# STM32.net
KiCad netlist of a schematic drawn in Altium Designer
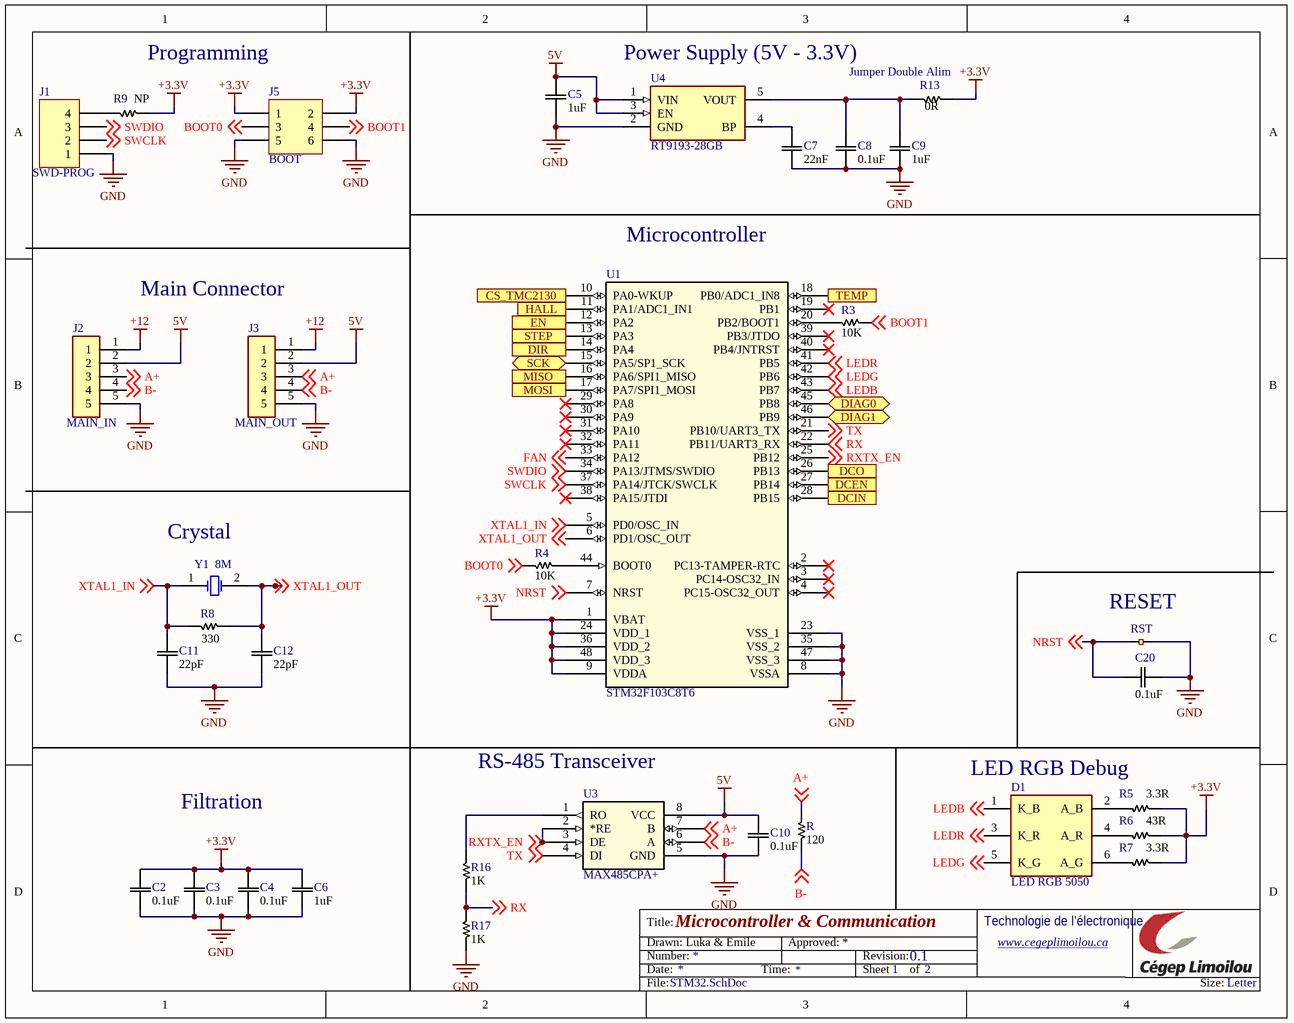
[diagram p0: STM32.SchDoc]

(export (version "E")
  (design (tool "Eeschema 10.0.6"))
  (components
    (comp (ref "C2")
      (value "0.1uF")
      (footprint "0603")
      (description "Capacitor SMD 0603")
      (fields
        (field (name "MANUFACTURER_PART_NUMBER") "12065A820JAT2A")
        (field (name "Comment") "Capacitor 0603")
        (field (name "COPYRIGHT") "Copyright (C) 2018 Accelerated Designs. All rights reserved")
      )
      (libsource (lib "Schematic_Emile") (part "Capacitor 1206"))
    )
    (comp (ref "C3")
      (value "0.1uF")
      (footprint "0603")
      (description "Capacitor SMD 0603")
      (fields
        (field (name "MANUFACTURER_PART_NUMBER") "12065A820JAT2A")
        (field (name "Comment") "Capacitor 0603")
        (field (name "COPYRIGHT") "Copyright (C) 2018 Accelerated Designs. All rights reserved")
      )
      (libsource (lib "Schematic_Emile") (part "Capacitor 1206"))
    )
    (comp (ref "C4")
      (value "0.1uF")
      (footprint "0603")
      (description "Capacitor SMD 0603")
      (fields
        (field (name "MANUFACTURER_PART_NUMBER") "12065A820JAT2A")
        (field (name "Comment") "Capacitor 0603")
        (field (name "COPYRIGHT") "Copyright (C) 2018 Accelerated Designs. All rights reserved")
      )
      (libsource (lib "Schematic_Emile") (part "Capacitor 1206"))
    )
    (comp (ref "C5")
      (value "1uF")
      (footprint "0603")
      (description "Capacitor SMD 0603")
      (fields
        (field (name "MANUFACTURER_PART_NUMBER") "12065A820JAT2A")
        (field (name "Comment") "Capacitor 0603")
        (field (name "COPYRIGHT") "Copyright (C) 2018 Accelerated Designs. All rights reserved")
      )
      (libsource (lib "Schematic_Emile") (part "Capacitor 1206"))
    )
    (comp (ref "C6")
      (value "1uF")
      (footprint "0603")
      (description "Capacitor SMD 0603")
      (fields
        (field (name "MANUFACTURER_PART_NUMBER") "12065A820JAT2A")
        (field (name "Comment") "Capacitor 0603")
        (field (name "COPYRIGHT") "Copyright (C) 2018 Accelerated Designs. All rights reserved")
      )
      (libsource (lib "Schematic_Emile") (part "Capacitor 1206"))
    )
    (comp (ref "C7")
      (value "22nF")
      (footprint "0603")
      (description "Capacitor SMD 0603")
      (fields
        (field (name "MANUFACTURER_PART_NUMBER") "12065A820JAT2A")
        (field (name "Comment") "Capacitor 0603")
        (field (name "COPYRIGHT") "Copyright (C) 2018 Accelerated Designs. All rights reserved")
      )
      (libsource (lib "Schematic_Emile") (part "Capacitor 1206"))
    )
    (comp (ref "C8")
      (value "0.1uF")
      (footprint "0603")
      (description "Capacitor SMD 0603")
      (fields
        (field (name "MANUFACTURER_PART_NUMBER") "12065A820JAT2A")
        (field (name "Comment") "Capacitor 0603")
        (field (name "COPYRIGHT") "Copyright (C) 2018 Accelerated Designs. All rights reserved")
      )
      (libsource (lib "Schematic_Emile") (part "Capacitor 1206"))
    )
    (comp (ref "C9")
      (value "1uF")
      (footprint "0603")
      (description "Capacitor SMD 0603")
      (fields
        (field (name "MANUFACTURER_PART_NUMBER") "12065A820JAT2A")
        (field (name "Comment") "Capacitor 0603")
        (field (name "COPYRIGHT") "Copyright (C) 2018 Accelerated Designs. All rights reserved")
      )
      (libsource (lib "Schematic_Emile") (part "Capacitor 1206"))
    )
    (comp (ref "C10")
      (value "0.1uF")
      (footprint "0603")
      (description "Capacitor SMD 0603")
      (fields
        (field (name "MANUFACTURER_PART_NUMBER") "12065A820JAT2A")
        (field (name "Comment") "Capacitor 0603")
        (field (name "COPYRIGHT") "Copyright (C) 2018 Accelerated Designs. All rights reserved")
      )
      (libsource (lib "Schematic_Emile") (part "Capacitor 1206"))
    )
    (comp (ref "C11")
      (value "22pF")
      (footprint "0603")
      (description "Capacitor SMD 0603")
      (fields
        (field (name "MANUFACTURER_PART_NUMBER") "12065A820JAT2A")
        (field (name "Comment") "Capacitor 0603")
        (field (name "COPYRIGHT") "Copyright (C) 2018 Accelerated Designs. All rights reserved")
      )
      (libsource (lib "Schematic_Emile") (part "Capacitor 1206"))
    )
    (comp (ref "C12")
      (value "22pF")
      (footprint "0603")
      (description "Capacitor SMD 0603")
      (fields
        (field (name "MANUFACTURER_PART_NUMBER") "12065A820JAT2A")
        (field (name "Comment") "Capacitor 0603")
        (field (name "COPYRIGHT") "Copyright (C) 2018 Accelerated Designs. All rights reserved")
      )
      (libsource (lib "Schematic_Emile") (part "Capacitor 1206"))
    )
    (comp (ref "C20")
      (value "0.1uF")
      (footprint "0603")
      (description "Capacitor SMD 0603")
      (fields
        (field (name "MANUFACTURER_PART_NUMBER") "12065A820JAT2A")
        (field (name "Comment") "Capacitor 0603")
        (field (name "COPYRIGHT") "Copyright (C) 2018 Accelerated Designs. All rights reserved")
      )
      (libsource (lib "Schematic_Emile") (part "Capacitor 1206"))
    )
    (comp (ref "D1")
      (value "LED RGB 5050")
      (footprint "LED 5050")
      (description "LED")
      (fields
        (field (name "MANUFACTURER_PART_NUMBER") "150505M173300")
        (field (name "MOUSER PART NUMBER") "710-150505M173300")
      )
      (libsource (lib "Schematic_Emile") (part "150505M173300"))
    )
    (comp (ref "J1")
      (value "SWD-PROG")
      (footprint "HDR1X4")
      (description "Header, 4-Pin")
      (fields (field (name "PUBLISHER") "Altium Limited"))
      (libsource (lib "Miscellaneous Connectors") (part "Header 4"))
    )
    (comp (ref "J2")
      (value "MAIN_IN")
      (footprint "JST 5POS 2.5mm 90°")
      (description "Connector")
      (fields (field (name "MANUFACTURER_PART_NUMBER") "S5B-XH-A-1(LF)(SN)"))
      (libsource (lib "Schematic_Emile") (part "JST 5POS"))
    )
    (comp (ref "J3")
      (value "MAIN_OUT")
      (footprint "JST 5POS 2.5mm 90°")
      (description "Connector")
      (fields (field (name "MANUFACTURER_PART_NUMBER") "S5B-XH-A-1(LF)(SN)"))
      (libsource (lib "Schematic_Emile") (part "JST 5POS"))
    )
    (comp (ref "J5")
      (value "BOOT")
      (footprint "Header 3x2 1.27mm SMD")
      (description "Header, 3-Pin, Dual row")
      (fields (field (name "PUBLISHER") "Altium Limited"))
      (libsource (lib "Miscellaneous Connectors") (part "Header 3X2"))
    )
    (comp (ref "R")
      (value "120")
      (footprint "0603")
      (description "Resistor 0603 SMD")
      (fields
        (field (name "MANUFACTURER_PART_NUMBER") "ERJ8CWFR024V")
        (field (name "Comment") "Resistor 0603")
        (field (name "COPYRIGHT") "Copyright (C) 2018 Accelerated Designs. All rights reserved")
      )
      (libsource (lib "Schematic_Emile") (part "Resistor 1206"))
    )
    (comp (ref "R3")
      (value "10K")
      (footprint "0603")
      (description "Resistor 0603 SMD")
      (fields
        (field (name "MANUFACTURER_PART_NUMBER") "ERJ8CWFR024V")
        (field (name "Comment") "Resistor 0603")
        (field (name "COPYRIGHT") "Copyright (C) 2018 Accelerated Designs. All rights reserved")
      )
      (libsource (lib "Schematic_Emile") (part "Resistor 1206"))
    )
    (comp (ref "R4")
      (value "10K")
      (footprint "0603")
      (description "Resistor 0603 SMD")
      (fields
        (field (name "MANUFACTURER_PART_NUMBER") "ERJ8CWFR024V")
        (field (name "Comment") "Resistor 0603")
        (field (name "COPYRIGHT") "Copyright (C) 2018 Accelerated Designs. All rights reserved")
      )
      (libsource (lib "Schematic_Emile") (part "Resistor 1206"))
    )
    (comp (ref "R5")
      (value "3.3R")
      (footprint "0603")
      (description "Resistor 0603 SMD")
      (fields
        (field (name "MANUFACTURER_PART_NUMBER") "ERJ8CWFR024V")
        (field (name "Comment") "Resistor 0603")
        (field (name "COPYRIGHT") "Copyright (C) 2018 Accelerated Designs. All rights reserved")
      )
      (libsource (lib "Schematic_Emile") (part "Resistor 1206"))
    )
    (comp (ref "R6")
      (value "43R")
      (footprint "0603")
      (description "Resistor 0603 SMD")
      (fields
        (field (name "MANUFACTURER_PART_NUMBER") "ERJ8CWFR024V")
        (field (name "Comment") "Resistor 0603")
        (field (name "COPYRIGHT") "Copyright (C) 2018 Accelerated Designs. All rights reserved")
      )
      (libsource (lib "Schematic_Emile") (part "Resistor 1206"))
    )
    (comp (ref "R7")
      (value "3.3R")
      (footprint "0603")
      (description "Resistor 0603 SMD")
      (fields
        (field (name "MANUFACTURER_PART_NUMBER") "ERJ8CWFR024V")
        (field (name "Comment") "Resistor 0603")
        (field (name "COPYRIGHT") "Copyright (C) 2018 Accelerated Designs. All rights reserved")
      )
      (libsource (lib "Schematic_Emile") (part "Resistor 1206"))
    )
    (comp (ref "R8")
      (value "330")
      (footprint "0603")
      (description "Resistor 0603 SMD")
      (fields
        (field (name "MANUFACTURER_PART_NUMBER") "ERJ8CWFR024V")
        (field (name "Comment") "Resistor 0603")
        (field (name "COPYRIGHT") "Copyright (C) 2018 Accelerated Designs. All rights reserved")
      )
      (libsource (lib "Schematic_Emile") (part "Resistor 1206"))
    )
    (comp (ref "R9")
      (value "NP")
      (footprint "0603")
      (description "Resistor 0603 SMD")
      (fields
        (field (name "MANUFACTURER_PART_NUMBER") "ERJ8CWFR024V")
        (field (name "Comment") "Jumper 0603")
        (field (name "COPYRIGHT") "Copyright (C) 2018 Accelerated Designs. All rights reserved")
      )
      (libsource (lib "Schematic_Emile") (part "Resistor 1206"))
    )
    (comp (ref "R13")
      (value "0R")
      (footprint "0603")
      (description "Resistor 1206 SMD")
      (fields
        (field (name "MANUFACTURER_PART_NUMBER") "ERJ8CWFR024V")
        (field (name "Comment") "Jumper 0603")
        (field (name "COPYRIGHT") "Copyright (C) 2018 Accelerated Designs. All rights reserved")
      )
      (libsource (lib "Schematic_Emile") (part "Resistor 1206"))
    )
    (comp (ref "R16")
      (value "1K")
      (footprint "0603")
      (description "Resistor 0603 SMD")
      (fields
        (field (name "MANUFACTURER_PART_NUMBER") "ERJ8CWFR024V")
        (field (name "Comment") "Resistor 0603")
        (field (name "COPYRIGHT") "Copyright (C) 2018 Accelerated Designs. All rights reserved")
      )
      (libsource (lib "Schematic_Emile") (part "Resistor 1206"))
    )
    (comp (ref "R17")
      (value "1K")
      (footprint "0603")
      (description "Resistor 0603 SMD")
      (fields
        (field (name "MANUFACTURER_PART_NUMBER") "ERJ8CWFR024V")
        (field (name "Comment") "Resistor 0603")
        (field (name "COPYRIGHT") "Copyright (C) 2018 Accelerated Designs. All rights reserved")
      )
      (libsource (lib "Schematic_Emile") (part "Resistor 1206"))
    )
    (comp (ref "RST")
      (value "PAD RST")
      (footprint "PAD")
      (description "SMD Pad for contact")
      (libsource (lib "Schematic_Emile") (part "PAD"))
    )
    (comp (ref "U1")
      (value "STM32F103C8T6")
      (footprint "LQFP-48")
      (description "Integrated Circuit STM32")
      (fields (field (name "COPYRIGHT") "Copyright (C) 2018 Accelerated Designs. All rights reserved"))
      (libsource (lib "Schematic_Emile") (part "STM32F103C8T6"))
    )
    (comp (ref "U3")
      (value "MAX485CPA+")
      (footprint "DIP 8 - 3D")
      (description "RS485 Communication")
      (fields (field (name "COPYRIGHT") "Copyright (C) 2018 Accelerated Designs. All rights reserved"))
      (libsource (lib "Schematic_Emile") (part "MAX485CPA+"))
    )
    (comp (ref "U4")
      (value "RT9193-28GB")
      (footprint "SamacSys:SOT94P279X130-5N")
      (description "Voltage Regulator 3.3V")
      (libsource (lib "Schematic_Emile") (part "RT9193-28GB"))
    )
    (comp (ref "Y1")
      (value "8M")
      (footprint "ATS080B-E")
      (description "Crystal Oscillator")
      (fields (field (name "PUBLISHER") "Altium Limited"))
      (libsource (lib "Miscellaneous Devices") (part "XTAL"))
    )
  )
  (nets
    (net (code "1") (name "+3.3V") (class "Default")
      (node (ref "C2") (pin "2") (pinfunction "2_2") (pintype "passive"))
      (node (ref "C3") (pin "2") (pinfunction "2_2") (pintype "passive"))
      (node (ref "C4") (pin "2") (pinfunction "2_2") (pintype "passive"))
      (node (ref "C6") (pin "2") (pinfunction "2_2") (pintype "passive"))
      (node (ref "J5") (pin "1") (pinfunction "1_1") (pintype "passive"))
      (node (ref "J5") (pin "2") (pinfunction "2_2") (pintype "passive"))
      (node (ref "R13") (pin "2") (pinfunction "2_2") (pintype "passive"))
      (node (ref "R5") (pin "2") (pinfunction "2_2") (pintype "passive"))
      (node (ref "R6") (pin "2") (pinfunction "2_2") (pintype "passive"))
      (node (ref "R7") (pin "2") (pinfunction "2_2") (pintype "passive"))
      (node (ref "R9") (pin "2") (pinfunction "2_2") (pintype "passive"))
      (node (ref "U1") (pin "1") (pinfunction "VBAT_1") (pintype "power_in"))
      (node (ref "U1") (pin "24") (pinfunction "VDD_1_24") (pintype "power_in"))
      (node (ref "U1") (pin "36") (pinfunction "VDD_2_36") (pintype "power_in"))
      (node (ref "U1") (pin "48") (pinfunction "VDD_3_48") (pintype "power_in"))
      (node (ref "U1") (pin "9") (pinfunction "VDDA_9") (pintype "power_in"))
    )
    (net (code "2") (name "+12") (class "Default")
      (node (ref "J2") (pin "1") (pinfunction "1_1") (pintype "passive"))
      (node (ref "J3") (pin "1") (pinfunction "1_1") (pintype "passive"))
    )
    (net (code "3") (name "/CS_TMC2130") (class "Default")
      (node (ref "U1") (pin "10") (pinfunction "PA0-WKUP_10") (pintype "bidirectional"))
    )
    (net (code "4") (name "/DCEN") (class "Default")
      (node (ref "U1") (pin "27") (pinfunction "PB14_27") (pintype "bidirectional"))
    )
    (net (code "5") (name "/DCIN") (class "Default")
      (node (ref "U1") (pin "28") (pinfunction "PB15_28") (pintype "bidirectional"))
    )
    (net (code "6") (name "/DCO") (class "Default")
      (node (ref "U1") (pin "26") (pinfunction "PB13_26") (pintype "bidirectional"))
    )
    (net (code "7") (name "/DIAG0") (class "Default")
      (node (ref "U1") (pin "45") (pinfunction "PB8_45") (pintype "bidirectional"))
    )
    (net (code "8") (name "/DIAG1") (class "Default")
      (node (ref "U1") (pin "46") (pinfunction "PB9_46") (pintype "bidirectional"))
    )
    (net (code "9") (name "/DIR") (class "Default")
      (node (ref "U1") (pin "14") (pinfunction "PA4_14") (pintype "bidirectional"))
    )
    (net (code "10") (name "/EN") (class "Default")
      (node (ref "U1") (pin "12") (pinfunction "PA2_12") (pintype "bidirectional"))
    )
    (net (code "11") (name "/HALL") (class "Default")
      (node (ref "U1") (pin "11") (pinfunction "PA1/ADC1_IN1_11") (pintype "bidirectional"))
    )
    (net (code "12") (name "/MISO") (class "Default")
      (node (ref "U1") (pin "16") (pinfunction "PA6/SPI1_MISO_16") (pintype "bidirectional"))
    )
    (net (code "13") (name "/MOSI") (class "Default")
      (node (ref "U1") (pin "17") (pinfunction "PA7/SPI1_MOSI_17") (pintype "bidirectional"))
    )
    (net (code "14") (name "/SCK") (class "Default")
      (node (ref "U1") (pin "15") (pinfunction "PA5/SP1_SCK_15") (pintype "bidirectional"))
    )
    (net (code "15") (name "/STEP") (class "Default")
      (node (ref "U1") (pin "13") (pinfunction "PA3_13") (pintype "bidirectional"))
    )
    (net (code "16") (name "/TEMP") (class "Default")
      (node (ref "U1") (pin "18") (pinfunction "PB0/ADC1_IN8_18") (pintype "bidirectional"))
    )
    (net (code "17") (name "5V") (class "Default")
      (node (ref "C10") (pin "2") (pinfunction "2_2") (pintype "passive"))
      (node (ref "C5") (pin "2") (pinfunction "2_2") (pintype "passive"))
      (node (ref "J2") (pin "2") (pinfunction "2_2") (pintype "passive"))
      (node (ref "J3") (pin "2") (pinfunction "2_2") (pintype "passive"))
      (node (ref "U3") (pin "8") (pinfunction "VCC_8") (pintype "power_in"))
      (node (ref "U4") (pin "1") (pinfunction "VIN_1") (pintype "input"))
      (node (ref "U4") (pin "3") (pinfunction "EN_3") (pintype "input"))
    )
    (net (code "18") (name "A+") (class "Default")
      (node (ref "J2") (pin "3") (pinfunction "3_3") (pintype "passive"))
      (node (ref "J3") (pin "3") (pinfunction "3_3") (pintype "passive"))
      (node (ref "R") (pin "2") (pinfunction "2_2") (pintype "passive"))
      (node (ref "U3") (pin "7") (pinfunction "B_7") (pintype "bidirectional"))
    )
    (net (code "19") (name "B-") (class "Default")
      (node (ref "J2") (pin "4") (pinfunction "4_4") (pintype "passive"))
      (node (ref "J3") (pin "4") (pinfunction "4_4") (pintype "passive"))
      (node (ref "R") (pin "1") (pinfunction "1_1") (pintype "passive"))
      (node (ref "U3") (pin "6") (pinfunction "A_6") (pintype "bidirectional"))
    )
    (net (code "20") (name "BOOT0") (class "Default")
      (node (ref "J5") (pin "3") (pinfunction "3_3") (pintype "passive"))
      (node (ref "R4") (pin "1") (pinfunction "1_1") (pintype "passive"))
    )
    (net (code "21") (name "BOOT1") (class "Default")
      (node (ref "J5") (pin "4") (pinfunction "4_4") (pintype "passive"))
      (node (ref "R3") (pin "2") (pinfunction "2_2") (pintype "passive"))
    )
    (net (code "22") (name "FAN") (class "Default")
      (node (ref "U1") (pin "33") (pinfunction "PA12_33") (pintype "bidirectional"))
    )
    (net (code "23") (name "GND") (class "Default")
      (node (ref "C10") (pin "1") (pinfunction "1_1") (pintype "passive"))
      (node (ref "C11") (pin "1") (pinfunction "1_1") (pintype "passive"))
      (node (ref "C12") (pin "1") (pinfunction "1_1") (pintype "passive"))
      (node (ref "C2") (pin "1") (pinfunction "1_1") (pintype "passive"))
      (node (ref "C20") (pin "1") (pinfunction "1_1") (pintype "passive"))
      (node (ref "C3") (pin "1") (pinfunction "1_1") (pintype "passive"))
      (node (ref "C4") (pin "1") (pinfunction "1_1") (pintype "passive"))
      (node (ref "C5") (pin "1") (pinfunction "1_1") (pintype "passive"))
      (node (ref "C6") (pin "1") (pinfunction "1_1") (pintype "passive"))
      (node (ref "C7") (pin "1") (pinfunction "1_1") (pintype "passive"))
      (node (ref "C8") (pin "1") (pinfunction "1_1") (pintype "passive"))
      (node (ref "C9") (pin "1") (pinfunction "1_1") (pintype "passive"))
      (node (ref "J1") (pin "1") (pinfunction "1_1") (pintype "passive"))
      (node (ref "J2") (pin "5") (pinfunction "5_5") (pintype "passive"))
      (node (ref "J3") (pin "5") (pinfunction "5_5") (pintype "passive"))
      (node (ref "J5") (pin "5") (pinfunction "5_5") (pintype "passive"))
      (node (ref "J5") (pin "6") (pinfunction "6_6") (pintype "passive"))
      (node (ref "R17") (pin "2") (pinfunction "2_2") (pintype "passive"))
      (node (ref "RST") (pin "1") (pinfunction "1_1") (pintype "passive"))
      (node (ref "U1") (pin "23") (pinfunction "VSS_1_23") (pintype "power_in"))
      (node (ref "U1") (pin "35") (pinfunction "VSS_2_35") (pintype "power_in"))
      (node (ref "U1") (pin "47") (pinfunction "VSS_3_47") (pintype "power_in"))
      (node (ref "U1") (pin "8") (pinfunction "VSSA_8") (pintype "power_in"))
      (node (ref "U3") (pin "5") (pinfunction "GND_5") (pintype "power_in"))
      (node (ref "U4") (pin "2") (pinfunction "GND_2") (pintype "power_in"))
    )
    (net (code "24") (name "LEDB") (class "Default")
      (node (ref "D1") (pin "1") (pinfunction "K_B_1") (pintype "passive"))
      (node (ref "U1") (pin "43") (pinfunction "PB7_43") (pintype "bidirectional"))
    )
    (net (code "25") (name "LEDG") (class "Default")
      (node (ref "D1") (pin "5") (pinfunction "K_G_5") (pintype "passive"))
      (node (ref "U1") (pin "42") (pinfunction "PB6_42") (pintype "bidirectional"))
    )
    (net (code "26") (name "LEDR") (class "Default")
      (node (ref "D1") (pin "3") (pinfunction "K_R_3") (pintype "passive"))
      (node (ref "U1") (pin "41") (pinfunction "PB5_41") (pintype "bidirectional"))
    )
    (net (code "27") (name "NRST") (class "Default")
      (node (ref "C20") (pin "2") (pinfunction "2_2") (pintype "passive"))
      (node (ref "RST") (pin "2") (pinfunction "2_2") (pintype "passive"))
      (node (ref "U1") (pin "7") (pinfunction "NRST_7") (pintype "bidirectional"))
    )
    (net (code "28") (name "Net-(D1-A_B)") (class "Default")
      (node (ref "D1") (pin "2") (pinfunction "A_B_2") (pintype "passive"))
      (node (ref "R5") (pin "1") (pinfunction "1_1") (pintype "passive"))
    )
    (net (code "29") (name "Net-(D1-A_G)") (class "Default")
      (node (ref "D1") (pin "6") (pinfunction "A_G_6") (pintype "passive"))
      (node (ref "R7") (pin "1") (pinfunction "1_1") (pintype "passive"))
    )
    (net (code "30") (name "Net-(D1-A_R)") (class "Default")
      (node (ref "D1") (pin "4") (pinfunction "A_R_4") (pintype "passive"))
      (node (ref "R6") (pin "1") (pinfunction "1_1") (pintype "passive"))
    )
    (net (code "31") (name "Net-(J1-Pad4)") (class "Default")
      (node (ref "J1") (pin "4") (pinfunction "4_4") (pintype "passive"))
      (node (ref "R9") (pin "1") (pinfunction "1_1") (pintype "passive"))
    )
    (net (code "32") (name "Net-(U1-BOOT0)") (class "Default")
      (node (ref "R4") (pin "2") (pinfunction "2_2") (pintype "passive"))
      (node (ref "U1") (pin "44") (pinfunction "BOOT0_44") (pintype "input"))
    )
    (net (code "33") (name "Net-(U1-PB2{slash}BOOT1)") (class "Default")
      (node (ref "R3") (pin "1") (pinfunction "1_1") (pintype "passive"))
      (node (ref "U1") (pin "20") (pinfunction "PB2/BOOT1_20") (pintype "bidirectional"))
    )
    (net (code "34") (name "Net-(U3-RO)") (class "Default")
      (node (ref "R16") (pin "1") (pinfunction "1_1") (pintype "passive"))
      (node (ref "U3") (pin "1") (pinfunction "RO_1") (pintype "output"))
    )
    (net (code "35") (name "Net-(U4-BP)") (class "Default")
      (node (ref "C7") (pin "2") (pinfunction "2_2") (pintype "passive"))
      (node (ref "U4") (pin "4") (pinfunction "BP_4") (pintype "passive"))
    )
    (net (code "36") (name "Net-(U4-VOUT)") (class "Default")
      (node (ref "C8") (pin "2") (pinfunction "2_2") (pintype "passive"))
      (node (ref "C9") (pin "2") (pinfunction "2_2") (pintype "passive"))
      (node (ref "R13") (pin "1") (pinfunction "1_1") (pintype "passive"))
      (node (ref "U4") (pin "5") (pinfunction "VOUT_5") (pintype "passive"))
    )
    (net (code "37") (name "RX") (class "Default")
      (node (ref "R16") (pin "2") (pinfunction "2_2") (pintype "passive"))
      (node (ref "R17") (pin "1") (pinfunction "1_1") (pintype "passive"))
      (node (ref "U1") (pin "22") (pinfunction "PB11/UART3_RX_22") (pintype "bidirectional"))
    )
    (net (code "38") (name "RXTX_EN") (class "Default")
      (node (ref "U1") (pin "25") (pinfunction "PB12_25") (pintype "bidirectional"))
      (node (ref "U3") (pin "2") (pinfunction "*RE_2") (pintype "input"))
      (node (ref "U3") (pin "3") (pinfunction "DE_3") (pintype "input"))
    )
    (net (code "39") (name "SWCLK") (class "Default")
      (node (ref "J1") (pin "2") (pinfunction "2_2") (pintype "passive"))
      (node (ref "U1") (pin "37") (pinfunction "PA14/JTCK/SWCLK_37") (pintype "bidirectional"))
    )
    (net (code "40") (name "SWDIO") (class "Default")
      (node (ref "J1") (pin "3") (pinfunction "3_3") (pintype "passive"))
      (node (ref "U1") (pin "34") (pinfunction "PA13/JTMS/SWDIO_34") (pintype "bidirectional"))
    )
    (net (code "41") (name "TX") (class "Default")
      (node (ref "U1") (pin "21") (pinfunction "PB10/UART3_TX_21") (pintype "bidirectional"))
      (node (ref "U3") (pin "4") (pinfunction "DI_4") (pintype "input"))
    )
    (net (code "42") (name "XTAL1_IN") (class "Default")
      (node (ref "C11") (pin "2") (pinfunction "2_2") (pintype "passive"))
      (node (ref "R8") (pin "1") (pinfunction "1_1") (pintype "passive"))
      (node (ref "U1") (pin "5") (pinfunction "PD0/OSC_IN_5") (pintype "bidirectional"))
      (node (ref "Y1") (pin "1") (pinfunction "OSC1_1") (pintype "passive"))
    )
    (net (code "43") (name "XTAL1_OUT") (class "Default")
      (node (ref "C12") (pin "2") (pinfunction "2_2") (pintype "passive"))
      (node (ref "R8") (pin "2") (pinfunction "2_2") (pintype "passive"))
      (node (ref "U1") (pin "6") (pinfunction "PD1/OSC_OUT_6") (pintype "bidirectional"))
      (node (ref "Y1") (pin "2") (pinfunction "OSC2_2") (pintype "passive"))
    )
    (net (code "44") (name "unconnected-(U1-PA8-Pad29)") (class "Default")
      (node (ref "U1") (pin "29") (pinfunction "PA8_29") (pintype "bidirectional+no_connect"))
    )
    (net (code "45") (name "unconnected-(U1-PA9-Pad30)") (class "Default")
      (node (ref "U1") (pin "30") (pinfunction "PA9_30") (pintype "bidirectional+no_connect"))
    )
    (net (code "46") (name "unconnected-(U1-PA10-Pad31)") (class "Default")
      (node (ref "U1") (pin "31") (pinfunction "PA10_31") (pintype "bidirectional+no_connect"))
    )
    (net (code "47") (name "unconnected-(U1-PA11-Pad32)") (class "Default")
      (node (ref "U1") (pin "32") (pinfunction "PA11_32") (pintype "bidirectional+no_connect"))
    )
    (net (code "48") (name "unconnected-(U1-PA15{slash}JTDI-Pad38)") (class "Default")
      (node (ref "U1") (pin "38") (pinfunction "PA15/JTDI_38") (pintype "bidirectional+no_connect"))
    )
    (net (code "49") (name "unconnected-(U1-PB1-Pad19)") (class "Default")
      (node (ref "U1") (pin "19") (pinfunction "PB1_19") (pintype "bidirectional+no_connect"))
    )
    (net (code "50") (name "unconnected-(U1-PB3{slash}JTDO-Pad39)") (class "Default")
      (node (ref "U1") (pin "39") (pinfunction "PB3/JTDO_39") (pintype "bidirectional+no_connect"))
    )
    (net (code "51") (name "unconnected-(U1-PB4{slash}JNTRST-Pad40)") (class "Default")
      (node (ref "U1") (pin "40") (pinfunction "PB4/JNTRST_40") (pintype "bidirectional+no_connect"))
    )
    (net (code "52") (name "unconnected-(U1-PC13-TAMPER-RTC-Pad2)") (class "Default")
      (node (ref "U1") (pin "2") (pinfunction "PC13-TAMPER-RTC_2") (pintype "bidirectional+no_connect"))
    )
    (net (code "53") (name "unconnected-(U1-PC14-OSC32_IN-Pad3)") (class "Default")
      (node (ref "U1") (pin "3") (pinfunction "PC14-OSC32_IN_3") (pintype "bidirectional+no_connect"))
    )
    (net (code "54") (name "unconnected-(U1-PC15-OSC32_OUT-Pad4)") (class "Default")
      (node (ref "U1") (pin "4") (pinfunction "PC15-OSC32_OUT_4") (pintype "bidirectional+no_connect"))
    )
  )
)
